# TPS92638_-_Breakout.net
KiCad netlist of a schematic drawn in EAGLE
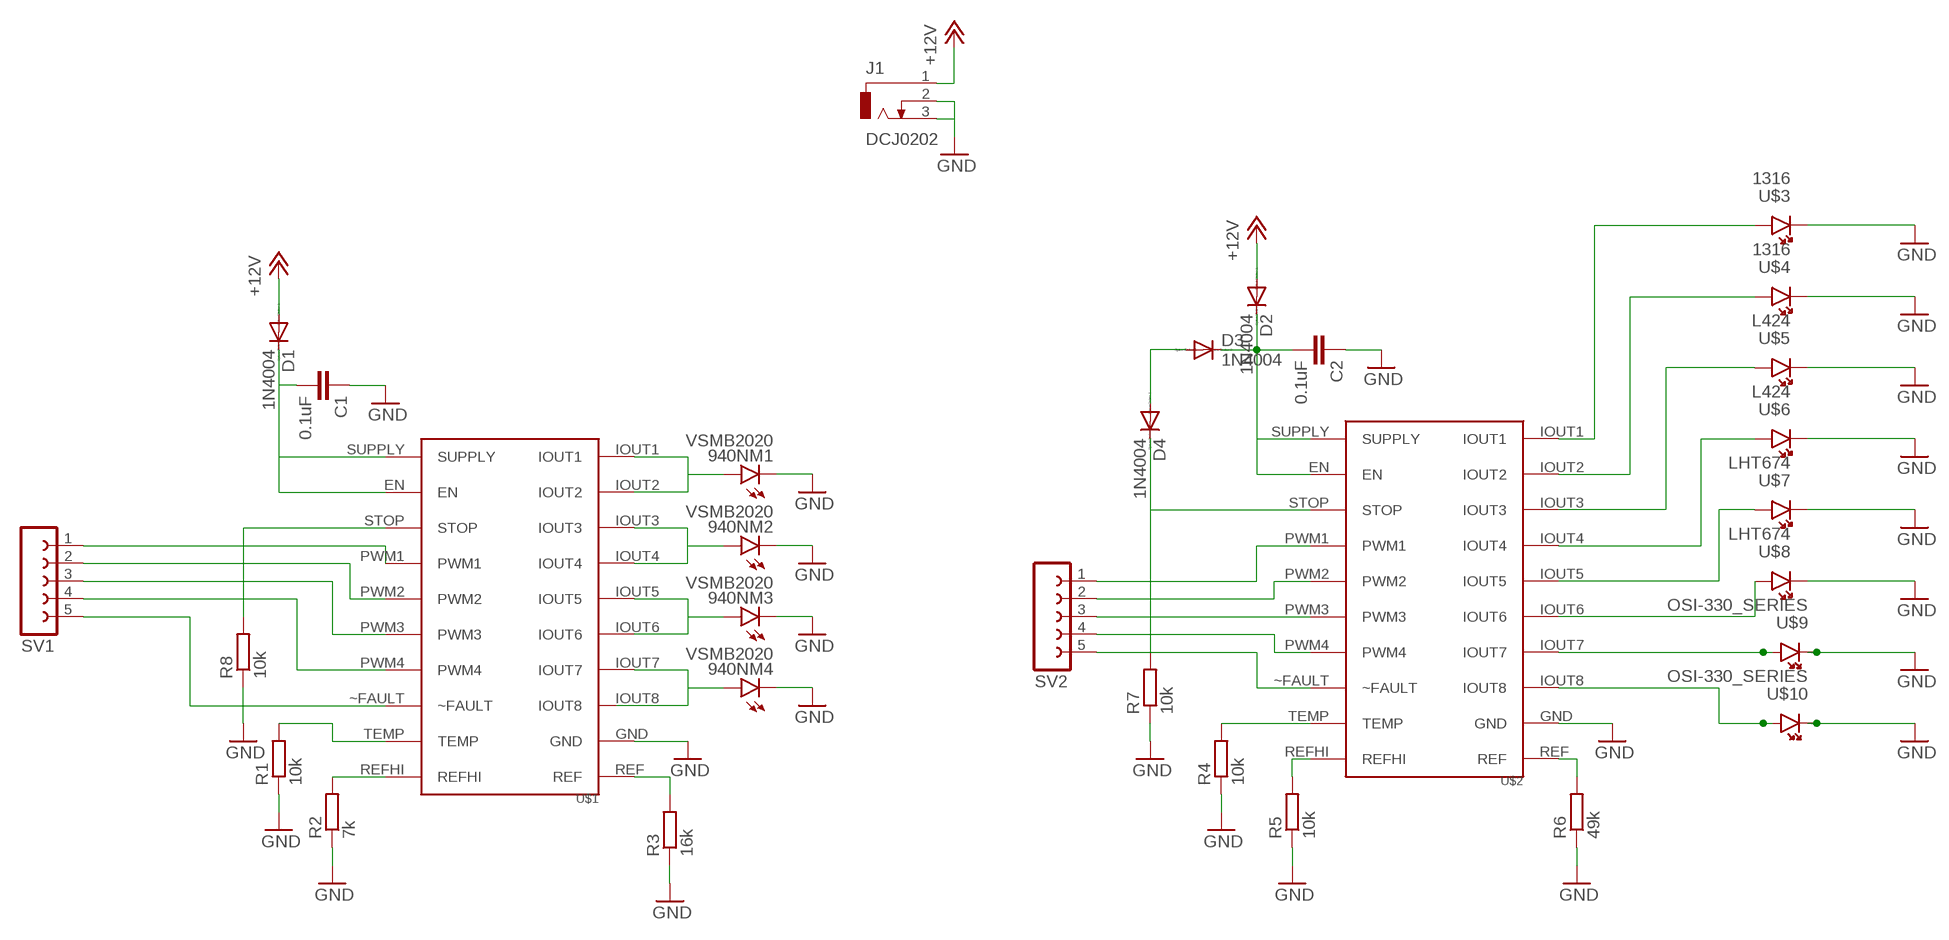
[diagram p0: schematic, sheet 1]

(export (version "E")
  (design (tool "Eeschema 10.0.6"))
  (components
    (comp (ref "940NM1")
      (value "VSMB2020")
      (footprint "eagle-import:GULLWING-2.3MM")
      (libsource (lib "eagle-import") (part "VSMB2020"))
    )
    (comp (ref "940NM2")
      (value "VSMB2020")
      (footprint "eagle-import:GULLWING-2.3MM")
      (libsource (lib "eagle-import") (part "VSMB2020"))
    )
    (comp (ref "940NM3")
      (value "VSMB2020")
      (footprint "eagle-import:GULLWING-2.3MM")
      (libsource (lib "eagle-import") (part "VSMB2020"))
    )
    (comp (ref "940NM4")
      (value "VSMB2020")
      (footprint "eagle-import:GULLWING-2.3MM")
      (libsource (lib "eagle-import") (part "VSMB2020"))
    )
    (comp (ref "C1")
      (value "0.1uF")
      (footprint "eagle-import:C0805")
      (libsource (lib "eagle-import") (part "C-EUC0805"))
    )
    (comp (ref "C2")
      (value "0.1uF")
      (footprint "eagle-import:C0805")
      (libsource (lib "eagle-import") (part "C-EUC0805"))
    )
    (comp (ref "D1")
      (value "1N4004")
      (footprint "eagle-import:DO41-10")
      (libsource (lib "eagle-import") (part "1N4004"))
    )
    (comp (ref "D2")
      (value "1N4004")
      (footprint "eagle-import:DO41-10")
      (libsource (lib "eagle-import") (part "1N4004"))
    )
    (comp (ref "D3")
      (value "1N4004")
      (footprint "eagle-import:DO41-10")
      (libsource (lib "eagle-import") (part "1N4004"))
    )
    (comp (ref "D4")
      (value "1N4004")
      (footprint "eagle-import:DO41-10")
      (libsource (lib "eagle-import") (part "1N4004"))
    )
    (comp (ref "J1")
      (value "DCJ0202")
      (footprint "eagle-import:DCJ0202")
      (libsource (lib "eagle-import") (part "DCJ0202"))
    )
    (comp (ref "R1")
      (value "10k")
      (footprint "eagle-import:M1206")
      (libsource (lib "eagle-import") (part "R-EU_M1206"))
    )
    (comp (ref "R2")
      (value "7k")
      (footprint "eagle-import:M1206")
      (libsource (lib "eagle-import") (part "R-EU_M1206"))
    )
    (comp (ref "R3")
      (value "16k")
      (footprint "eagle-import:M1206")
      (libsource (lib "eagle-import") (part "R-EU_M1206"))
    )
    (comp (ref "R4")
      (value "10k")
      (footprint "eagle-import:M1206")
      (libsource (lib "eagle-import") (part "R-EU_M1206"))
    )
    (comp (ref "R5")
      (value "10k")
      (footprint "eagle-import:M1206")
      (libsource (lib "eagle-import") (part "R-EU_M1206"))
    )
    (comp (ref "R6")
      (value "49k")
      (footprint "eagle-import:M1206")
      (libsource (lib "eagle-import") (part "R-EU_M1206"))
    )
    (comp (ref "R7")
      (value "10k")
      (footprint "eagle-import:M1206")
      (libsource (lib "eagle-import") (part "R-EU_M1206"))
    )
    (comp (ref "R8")
      (value "10k")
      (footprint "eagle-import:M1206")
      (libsource (lib "eagle-import") (part "R-EU_M1206"))
    )
    (comp (ref "SV1")
      (value "FE05-1")
      (footprint "eagle-import:FE05-1")
      (libsource (lib "eagle-import") (part "FE05-1"))
    )
    (comp (ref "SV2")
      (value "FE05-1")
      (footprint "eagle-import:FE05-1")
      (libsource (lib "eagle-import") (part "FE05-1"))
    )
    (comp (ref "U$1")
      (value "TPS92638")
      (footprint "eagle-import:TPS92638")
      (libsource (lib "eagle-import") (part "TPS92638"))
    )
    (comp (ref "U$2")
      (value "TPS92638")
      (footprint "eagle-import:TPS92638")
      (libsource (lib "eagle-import") (part "TPS92638"))
    )
    (comp (ref "U$3")
      (value "1316")
      (footprint "eagle-import:1316")
      (libsource (lib "eagle-import") (part "1316"))
    )
    (comp (ref "U$4")
      (value "1316")
      (footprint "eagle-import:1316")
      (libsource (lib "eagle-import") (part "1316"))
    )
    (comp (ref "U$5")
      (value "L424")
      (footprint "eagle-import:L424")
      (libsource (lib "eagle-import") (part "L424"))
    )
    (comp (ref "U$6")
      (value "L424")
      (footprint "eagle-import:L424")
      (libsource (lib "eagle-import") (part "L424"))
    )
    (comp (ref "U$7")
      (value "LHT674")
      (footprint "eagle-import:LHT674")
      (libsource (lib "eagle-import") (part "LHT674"))
    )
    (comp (ref "U$8")
      (value "LHT674")
      (footprint "eagle-import:LHT674")
      (libsource (lib "eagle-import") (part "LHT674"))
    )
    (comp (ref "U$9")
      (value "OSI-330_SERIES")
      (footprint "eagle-import:OSI-330_SERIES")
      (libsource (lib "eagle-import") (part "OSI-330_SERIES"))
    )
    (comp (ref "U$10")
      (value "OSI-330_SERIES")
      (footprint "eagle-import:OSI-330_SERIES")
      (libsource (lib "eagle-import") (part "OSI-330_SERIES"))
    )
  )
  (nets
    (net (code "1") (name "+12V") (class "Default")
      (node (ref "D1") (pin "A") (pinfunction "A_A") (pintype "passive"))
      (node (ref "D2") (pin "A") (pinfunction "A_A") (pintype "passive"))
      (node (ref "J1") (pin "1") (pinfunction "1_1") (pintype "passive"))
    )
    (net (code "2") (name "GND") (class "Default")
      (node (ref "940NM1") (pin "P$2") (pinfunction "C_P$2") (pintype "passive"))
      (node (ref "940NM2") (pin "P$2") (pinfunction "C_P$2") (pintype "passive"))
      (node (ref "940NM3") (pin "P$2") (pinfunction "C_P$2") (pintype "passive"))
      (node (ref "940NM4") (pin "P$2") (pinfunction "C_P$2") (pintype "passive"))
      (node (ref "C1") (pin "1") (pinfunction "1_1") (pintype "passive"))
      (node (ref "C2") (pin "1") (pinfunction "1_1") (pintype "passive"))
      (node (ref "J1") (pin "2") (pinfunction "2_2") (pintype "passive"))
      (node (ref "J1") (pin "3") (pinfunction "3_3") (pintype "passive"))
      (node (ref "R1") (pin "1") (pinfunction "1_1") (pintype "passive"))
      (node (ref "R2") (pin "1") (pinfunction "1_1") (pintype "passive"))
      (node (ref "R3") (pin "1") (pinfunction "1_1") (pintype "passive"))
      (node (ref "R4") (pin "1") (pinfunction "1_1") (pintype "passive"))
      (node (ref "R5") (pin "1") (pinfunction "1_1") (pintype "passive"))
      (node (ref "R6") (pin "1") (pinfunction "1_1") (pintype "passive"))
      (node (ref "R7") (pin "1") (pinfunction "1_1") (pintype "passive"))
      (node (ref "R8") (pin "1") (pinfunction "1_1") (pintype "passive"))
      (node (ref "U$1") (pin "GND") (pinfunction "GND_GND") (pintype "bidirectional"))
      (node (ref "U$10") (pin "CATHODE") (pinfunction "P$1_CATHODE") (pintype "passive"))
      (node (ref "U$2") (pin "GND") (pinfunction "GND_GND") (pintype "bidirectional"))
      (node (ref "U$3") (pin "CATHODE") (pinfunction "CATHODE_CATHODE") (pintype "passive"))
      (node (ref "U$4") (pin "CATHODE") (pinfunction "CATHODE_CATHODE") (pintype "passive"))
      (node (ref "U$5") (pin "CATHODE") (pinfunction "CATHODE_CATHODE") (pintype "passive"))
      (node (ref "U$6") (pin "CATHODE") (pinfunction "CATHODE_CATHODE") (pintype "passive"))
      (node (ref "U$7") (pin "CATHODE") (pinfunction "CATHODE_CATHODE") (pintype "passive"))
      (node (ref "U$8") (pin "CATHODE") (pinfunction "CATHODE_CATHODE") (pintype "passive"))
      (node (ref "U$9") (pin "CATHODE") (pinfunction "P$1_CATHODE") (pintype "passive"))
    )
    (net (code "3") (name "Net-(940NM1-A)") (class "Default")
      (node (ref "940NM1") (pin "P$1") (pinfunction "A_P$1") (pintype "passive"))
      (node (ref "U$1") (pin "IOUT1") (pinfunction "IOUT1_IOUT1") (pintype "bidirectional"))
      (node (ref "U$1") (pin "IOUT2") (pinfunction "IOUT2_IOUT2") (pintype "bidirectional"))
    )
    (net (code "4") (name "Net-(940NM2-A)") (class "Default")
      (node (ref "940NM2") (pin "P$1") (pinfunction "A_P$1") (pintype "passive"))
      (node (ref "U$1") (pin "IOUT3") (pinfunction "IOUT3_IOUT3") (pintype "bidirectional"))
      (node (ref "U$1") (pin "IOUT4") (pinfunction "IOUT4_IOUT4") (pintype "bidirectional"))
    )
    (net (code "5") (name "Net-(940NM3-A)") (class "Default")
      (node (ref "940NM3") (pin "P$1") (pinfunction "A_P$1") (pintype "passive"))
      (node (ref "U$1") (pin "IOUT5") (pinfunction "IOUT5_IOUT5") (pintype "bidirectional"))
      (node (ref "U$1") (pin "IOUT6") (pinfunction "IOUT6_IOUT6") (pintype "bidirectional"))
    )
    (net (code "6") (name "Net-(940NM4-A)") (class "Default")
      (node (ref "940NM4") (pin "P$1") (pinfunction "A_P$1") (pintype "passive"))
      (node (ref "U$1") (pin "IOUT7") (pinfunction "IOUT7_IOUT7") (pintype "bidirectional"))
    )
    (net (code "7") (name "Net-(C1-Pad2)") (class "Default")
      (node (ref "C1") (pin "2") (pinfunction "2_2") (pintype "passive"))
      (node (ref "D1") (pin "C") (pinfunction "C_C") (pintype "passive"))
      (node (ref "U$1") (pin "EN") (pinfunction "EN_EN") (pintype "bidirectional"))
      (node (ref "U$1") (pin "SUPPLY") (pinfunction "SUPPLY_SUPPLY") (pintype "bidirectional"))
    )
    (net (code "8") (name "Net-(C2-Pad2)") (class "Default")
      (node (ref "C2") (pin "2") (pinfunction "2_2") (pintype "passive"))
      (node (ref "D2") (pin "C") (pinfunction "C_C") (pintype "passive"))
      (node (ref "D3") (pin "C") (pinfunction "C_C") (pintype "passive"))
      (node (ref "U$2") (pin "EN") (pinfunction "EN_EN") (pintype "bidirectional"))
      (node (ref "U$2") (pin "SUPPLY") (pinfunction "SUPPLY_SUPPLY") (pintype "bidirectional"))
    )
    (net (code "9") (name "Net-(D3-PadA)") (class "Default")
      (node (ref "D3") (pin "A") (pinfunction "A_A") (pintype "passive"))
      (node (ref "D4") (pin "A") (pinfunction "A_A") (pintype "passive"))
    )
    (net (code "10") (name "Net-(D4-PadC)") (class "Default")
      (node (ref "D4") (pin "C") (pinfunction "C_C") (pintype "passive"))
      (node (ref "R7") (pin "2") (pinfunction "2_2") (pintype "passive"))
      (node (ref "U$2") (pin "STOP") (pinfunction "STOP_STOP") (pintype "bidirectional"))
    )
    (net (code "11") (name "Net-(R1-Pad2)") (class "Default")
      (node (ref "R1") (pin "2") (pinfunction "2_2") (pintype "passive"))
      (node (ref "U$1") (pin "TEMP") (pinfunction "TEMP_TEMP") (pintype "bidirectional"))
    )
    (net (code "12") (name "Net-(R2-Pad2)") (class "Default")
      (node (ref "R2") (pin "2") (pinfunction "2_2") (pintype "passive"))
      (node (ref "U$1") (pin "REFHI") (pinfunction "REFHI_REFHI") (pintype "bidirectional"))
    )
    (net (code "13") (name "Net-(R3-Pad2)") (class "Default")
      (node (ref "R3") (pin "2") (pinfunction "2_2") (pintype "passive"))
      (node (ref "U$1") (pin "REF") (pinfunction "REF_REF") (pintype "bidirectional"))
    )
    (net (code "14") (name "Net-(R4-Pad2)") (class "Default")
      (node (ref "R4") (pin "2") (pinfunction "2_2") (pintype "passive"))
      (node (ref "U$2") (pin "TEMP") (pinfunction "TEMP_TEMP") (pintype "bidirectional"))
    )
    (net (code "15") (name "Net-(R5-Pad2)") (class "Default")
      (node (ref "R5") (pin "2") (pinfunction "2_2") (pintype "passive"))
      (node (ref "U$2") (pin "REFHI") (pinfunction "REFHI_REFHI") (pintype "bidirectional"))
    )
    (net (code "16") (name "Net-(R6-Pad2)") (class "Default")
      (node (ref "R6") (pin "2") (pinfunction "2_2") (pintype "passive"))
      (node (ref "U$2") (pin "REF") (pinfunction "REF_REF") (pintype "bidirectional"))
    )
    (net (code "17") (name "Net-(R8-Pad2)") (class "Default")
      (node (ref "R8") (pin "2") (pinfunction "2_2") (pintype "passive"))
      (node (ref "U$1") (pin "STOP") (pinfunction "STOP_STOP") (pintype "bidirectional"))
    )
    (net (code "18") (name "Net-(SV1-Pad1)") (class "Default")
      (node (ref "SV1") (pin "1") (pinfunction "1_1") (pintype "passive"))
      (node (ref "U$1") (pin "PWM1") (pinfunction "PWM1_PWM1") (pintype "bidirectional"))
    )
    (net (code "19") (name "Net-(SV1-Pad2)") (class "Default")
      (node (ref "SV1") (pin "2") (pinfunction "2_2") (pintype "passive"))
      (node (ref "U$1") (pin "PWM2") (pinfunction "PWM2_PWM2") (pintype "bidirectional"))
    )
    (net (code "20") (name "Net-(SV1-Pad3)") (class "Default")
      (node (ref "SV1") (pin "3") (pinfunction "3_3") (pintype "passive"))
      (node (ref "U$1") (pin "PWM3") (pinfunction "PWM3_PWM3") (pintype "bidirectional"))
    )
    (net (code "21") (name "Net-(SV1-Pad4)") (class "Default")
      (node (ref "SV1") (pin "4") (pinfunction "4_4") (pintype "passive"))
      (node (ref "U$1") (pin "PWM4") (pinfunction "PWM4_PWM4") (pintype "bidirectional"))
    )
    (net (code "22") (name "Net-(SV2-Pad1)") (class "Default")
      (node (ref "SV2") (pin "1") (pinfunction "1_1") (pintype "passive"))
      (node (ref "U$2") (pin "PWM1") (pinfunction "PWM1_PWM1") (pintype "bidirectional"))
    )
    (net (code "23") (name "Net-(SV2-Pad2)") (class "Default")
      (node (ref "SV2") (pin "2") (pinfunction "2_2") (pintype "passive"))
      (node (ref "U$2") (pin "PWM2") (pinfunction "PWM2_PWM2") (pintype "bidirectional"))
    )
    (net (code "24") (name "Net-(SV2-Pad3)") (class "Default")
      (node (ref "SV2") (pin "3") (pinfunction "3_3") (pintype "passive"))
      (node (ref "U$2") (pin "PWM3") (pinfunction "PWM3_PWM3") (pintype "bidirectional"))
    )
    (net (code "25") (name "Net-(SV2-Pad4)") (class "Default")
      (node (ref "SV2") (pin "4") (pinfunction "4_4") (pintype "passive"))
      (node (ref "U$2") (pin "PWM4") (pinfunction "PWM4_PWM4") (pintype "bidirectional"))
    )
    (net (code "26") (name "Net-(U$1-~{FAULT})") (class "Default")
      (node (ref "SV1") (pin "5") (pinfunction "5_5") (pintype "passive"))
      (node (ref "U$1") (pin "~FAULT") (pinfunction "~{FAULT}_~FAULT") (pintype "bidirectional"))
    )
    (net (code "27") (name "Net-(U$2-PadIOUT1)") (class "Default")
      (node (ref "U$2") (pin "IOUT1") (pinfunction "IOUT1_IOUT1") (pintype "bidirectional"))
      (node (ref "U$3") (pin "ANODE") (pinfunction "ANODE_ANODE") (pintype "passive"))
    )
    (net (code "28") (name "Net-(U$2-PadIOUT2)") (class "Default")
      (node (ref "U$2") (pin "IOUT2") (pinfunction "IOUT2_IOUT2") (pintype "bidirectional"))
      (node (ref "U$4") (pin "ANODE") (pinfunction "ANODE_ANODE") (pintype "passive"))
    )
    (net (code "29") (name "Net-(U$2-PadIOUT3)") (class "Default")
      (node (ref "U$2") (pin "IOUT3") (pinfunction "IOUT3_IOUT3") (pintype "bidirectional"))
      (node (ref "U$5") (pin "ANODE") (pinfunction "ANODE_ANODE") (pintype "passive"))
    )
    (net (code "30") (name "Net-(U$2-PadIOUT4)") (class "Default")
      (node (ref "U$2") (pin "IOUT4") (pinfunction "IOUT4_IOUT4") (pintype "bidirectional"))
      (node (ref "U$6") (pin "ANODE") (pinfunction "ANODE_ANODE") (pintype "passive"))
    )
    (net (code "31") (name "Net-(U$2-PadIOUT5)") (class "Default")
      (node (ref "U$2") (pin "IOUT5") (pinfunction "IOUT5_IOUT5") (pintype "bidirectional"))
      (node (ref "U$7") (pin "ANODE") (pinfunction "ANODE_ANODE") (pintype "passive"))
    )
    (net (code "32") (name "Net-(U$2-PadIOUT6)") (class "Default")
      (node (ref "U$2") (pin "IOUT6") (pinfunction "IOUT6_IOUT6") (pintype "bidirectional"))
      (node (ref "U$8") (pin "ANODE") (pinfunction "ANODE_ANODE") (pintype "passive"))
    )
    (net (code "33") (name "Net-(U$2-PadIOUT7)") (class "Default")
      (node (ref "U$2") (pin "IOUT7") (pinfunction "IOUT7_IOUT7") (pintype "bidirectional"))
      (node (ref "U$9") (pin "ANODE") (pinfunction "ANODE_ANODE") (pintype "passive"))
    )
    (net (code "34") (name "Net-(U$2-~{FAULT})") (class "Default")
      (node (ref "SV2") (pin "5") (pinfunction "5_5") (pintype "passive"))
      (node (ref "U$2") (pin "~FAULT") (pinfunction "~{FAULT}_~FAULT") (pintype "bidirectional"))
    )
    (net (code "35") (name "Net-(U$10-PadANODE)") (class "Default")
      (node (ref "U$10") (pin "ANODE") (pinfunction "ANODE_ANODE") (pintype "passive"))
      (node (ref "U$2") (pin "IOUT8") (pinfunction "IOUT8_IOUT8") (pintype "bidirectional"))
    )
    (net (code "36") (name "unconnected-(U$1-PadIOUT8)") (class "Default")
      (node (ref "U$1") (pin "IOUT8") (pinfunction "IOUT8_IOUT8") (pintype "bidirectional"))
    )
  )
)
